# EMMC_with_rk399.net
KiCad netlist of a schematic drawn in Altium Designer
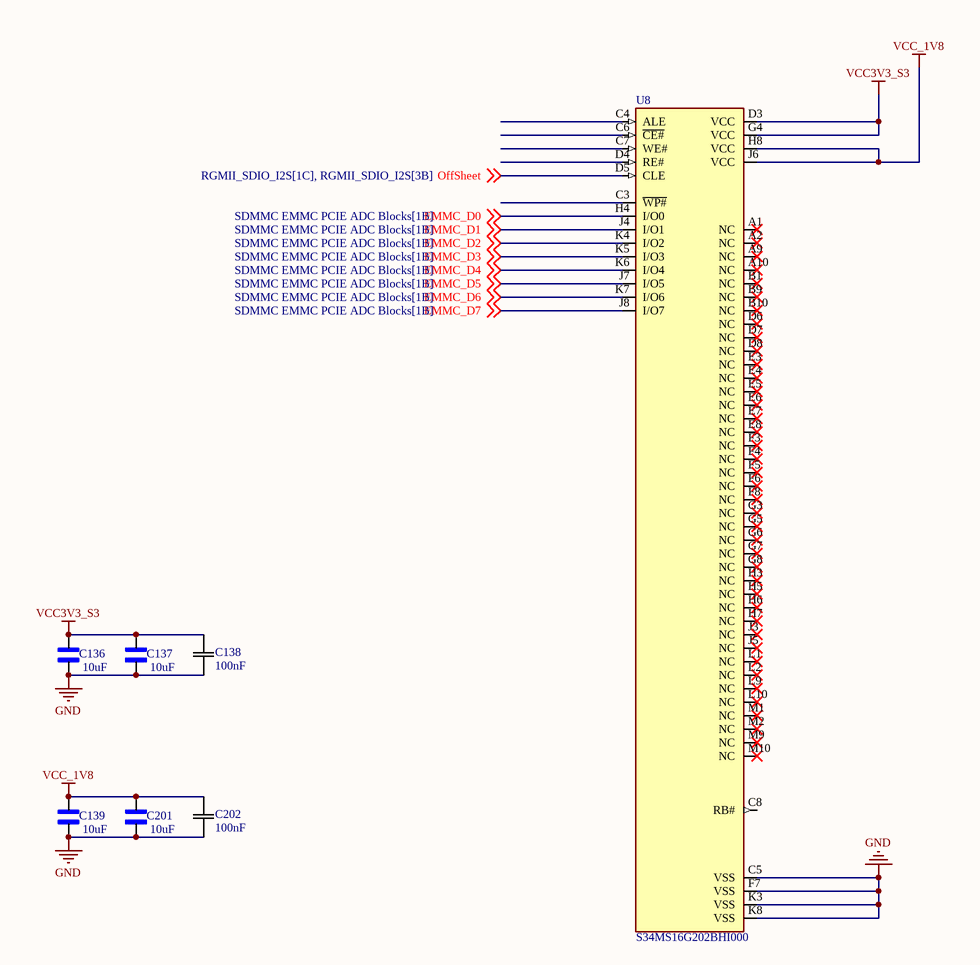
[diagram p0: EMMC with rk399.SchDoc]

(export (version "E")
  (design (tool "Eeschema 10.0.6"))
  (components
    (comp (ref "C136")
      (value "10uF")
      (footprint "CAPC1005X70N")
      (description "10 ÂµF Â±20% 6.3V Ceramic Capacitor X5R 0402 (1005 Metric)")
      (fields (field (name "MF") "Samsung") (field (name "MP") "CL05A106MQ5NUNC"))
      (libsource (lib "CL05A106MQ5NUNC") (part "CL05A106MQ5NUNC"))
    )
    (comp (ref "C137")
      (value "10uF")
      (footprint "CAPC1005X70N")
      (description "10 ÂµF Â±20% 6.3V Ceramic Capacitor X5R 0402 (1005 Metric)")
      (fields (field (name "MF") "Samsung") (field (name "MP") "CL05A106MQ5NUNC"))
      (libsource (lib "CL05A106MQ5NUNC") (part "CL05A106MQ5NUNC"))
    )
    (comp (ref "C138")
      (value "100nF")
      (footprint "CAP_1005_TDK")
      (description "Description")
      (fields
        (field (name "MANUFACTURER_PART_NUMBER") "C1005X7R1H104M050BB")
        (field (name "COPYRIGHT") "Copyright (C) 2025 Ultra Librarian. All rights reserved.")
      )
      (libsource (lib "C1005X7R1H104M050BB") (part "C1005X7R1H104M050BB"))
    )
    (comp (ref "C139")
      (value "10uF")
      (footprint "CAPC1005X70N")
      (description "10 ÂµF Â±20% 6.3V Ceramic Capacitor X5R 0402 (1005 Metric)")
      (fields (field (name "MF") "Samsung") (field (name "MP") "CL05A106MQ5NUNC"))
      (libsource (lib "CL05A106MQ5NUNC") (part "CL05A106MQ5NUNC"))
    )
    (comp (ref "C201")
      (value "10uF")
      (footprint "CAPC1005X70N")
      (description "10 ÂµF Â±20% 6.3V Ceramic Capacitor X5R 0402 (1005 Metric)")
      (fields (field (name "MF") "Samsung") (field (name "MP") "CL05A106MQ5NUNC"))
      (libsource (lib "CL05A106MQ5NUNC") (part "CL05A106MQ5NUNC"))
    )
    (comp (ref "C202")
      (value "100nF")
      (footprint "CAP_1005_TDK")
      (description "Description")
      (fields
        (field (name "MANUFACTURER_PART_NUMBER") "C1005X7R1H104M050BB")
        (field (name "COPYRIGHT") "Copyright (C) 2025 Ultra Librarian. All rights reserved.")
      )
      (libsource (lib "C1005X7R1H104M050BB") (part "C1005X7R1H104M050BB"))
    )
    (comp (ref "U8")
      (value "S34MS16G202BHI000")
      (footprint "BGA63C80P12X10_1100X900X120")
      (description "FLASH - NAND Memory IC 16Gb (4G x 4) Parallel 45 ns 63-BGA (11x9)")
      (fields (field (name "MF") "Cypress Semiconductor"))
      (libsource (lib "S34MS16G202BHI000") (part "S34MS16G202BHI000"))
    )
  )
  (nets
    (net (code "1") (name "EMMC_D0") (class "Default")
      (node (ref "U8") (pin "H4") (pinfunction "I/O0_H4") (pintype "bidirectional"))
    )
    (net (code "2") (name "EMMC_D1") (class "Default")
      (node (ref "U8") (pin "J4") (pinfunction "I/O1_J4") (pintype "bidirectional"))
    )
    (net (code "3") (name "EMMC_D2") (class "Default")
      (node (ref "U8") (pin "K4") (pinfunction "I/O2_K4") (pintype "bidirectional"))
    )
    (net (code "4") (name "EMMC_D3") (class "Default")
      (node (ref "U8") (pin "K5") (pinfunction "I/O3_K5") (pintype "bidirectional"))
    )
    (net (code "5") (name "EMMC_D4") (class "Default")
      (node (ref "U8") (pin "K6") (pinfunction "I/O4_K6") (pintype "bidirectional"))
    )
    (net (code "6") (name "EMMC_D5") (class "Default")
      (node (ref "U8") (pin "J7") (pinfunction "I/O5_J7") (pintype "bidirectional"))
    )
    (net (code "7") (name "EMMC_D6") (class "Default")
      (node (ref "U8") (pin "K7") (pinfunction "I/O6_K7") (pintype "bidirectional"))
    )
    (net (code "8") (name "EMMC_D7") (class "Default")
      (node (ref "U8") (pin "J8") (pinfunction "I/O7_J8") (pintype "bidirectional"))
    )
    (net (code "9") (name "GND") (class "Default")
      (node (ref "C136") (pin "1") (pinfunction "1_1") (pintype "passive"))
      (node (ref "C137") (pin "1") (pinfunction "1_1") (pintype "passive"))
      (node (ref "C138") (pin "2") (pinfunction "2_2") (pintype "passive"))
      (node (ref "C139") (pin "1") (pinfunction "1_1") (pintype "passive"))
      (node (ref "C201") (pin "1") (pinfunction "1_1") (pintype "passive"))
      (node (ref "C202") (pin "2") (pinfunction "2_2") (pintype "passive"))
      (node (ref "U8") (pin "C5") (pinfunction "VSS_C5") (pintype "power_in"))
      (node (ref "U8") (pin "F7") (pinfunction "VSS_F7") (pintype "power_in"))
      (node (ref "U8") (pin "K3") (pinfunction "VSS_K3") (pintype "power_in"))
      (node (ref "U8") (pin "K8") (pinfunction "VSS_K8") (pintype "power_in"))
    )
    (net (code "10") (name "OffSheet") (class "Default")
      (node (ref "U8") (pin "D5") (pinfunction "CLE_D5") (pintype "input"))
    )
    (net (code "11") (name "VCC3V3_S3") (class "Default")
      (node (ref "C136") (pin "2") (pinfunction "2_2") (pintype "passive"))
      (node (ref "C137") (pin "2") (pinfunction "2_2") (pintype "passive"))
      (node (ref "C138") (pin "1") (pinfunction "1_1") (pintype "passive"))
      (node (ref "U8") (pin "D3") (pinfunction "VCC_D3") (pintype "power_in"))
      (node (ref "U8") (pin "G4") (pinfunction "VCC_G4") (pintype "power_in"))
    )
    (net (code "12") (name "VCC_1V8") (class "Default")
      (node (ref "C139") (pin "2") (pinfunction "2_2") (pintype "passive"))
      (node (ref "C201") (pin "2") (pinfunction "2_2") (pintype "passive"))
      (node (ref "C202") (pin "1") (pinfunction "1_1") (pintype "passive"))
      (node (ref "U8") (pin "H8") (pinfunction "VCC_H8") (pintype "power_in"))
      (node (ref "U8") (pin "J6") (pinfunction "VCC_J6") (pintype "power_in"))
    )
    (net (code "13") (name "unconnected-(U8-ALE-PadC4)") (class "Default")
      (node (ref "U8") (pin "C4") (pinfunction "ALE_C4") (pintype "input"))
    )
    (net (code "14") (name "unconnected-(U8-NC-PadA1)") (class "Default")
      (node (ref "U8") (pin "A1") (pinfunction "NC_A1") (pintype "passive+no_connect"))
    )
    (net (code "15") (name "unconnected-(U8-NC-PadA2)") (class "Default")
      (node (ref "U8") (pin "A2") (pinfunction "NC_A2") (pintype "passive+no_connect"))
    )
    (net (code "16") (name "unconnected-(U8-NC-PadA9)") (class "Default")
      (node (ref "U8") (pin "A9") (pinfunction "NC_A9") (pintype "passive+no_connect"))
    )
    (net (code "17") (name "unconnected-(U8-NC-PadA10)") (class "Default")
      (node (ref "U8") (pin "A10") (pinfunction "NC_A10") (pintype "passive+no_connect"))
    )
    (net (code "18") (name "unconnected-(U8-NC-PadB1)") (class "Default")
      (node (ref "U8") (pin "B1") (pinfunction "NC_B1") (pintype "passive+no_connect"))
    )
    (net (code "19") (name "unconnected-(U8-NC-PadB9)") (class "Default")
      (node (ref "U8") (pin "B9") (pinfunction "NC_B9") (pintype "passive+no_connect"))
    )
    (net (code "20") (name "unconnected-(U8-NC-PadB10)") (class "Default")
      (node (ref "U8") (pin "B10") (pinfunction "NC_B10") (pintype "passive+no_connect"))
    )
    (net (code "21") (name "unconnected-(U8-NC-PadD6)") (class "Default")
      (node (ref "U8") (pin "D6") (pinfunction "NC_D6") (pintype "passive+no_connect"))
    )
    (net (code "22") (name "unconnected-(U8-NC-PadD7)") (class "Default")
      (node (ref "U8") (pin "D7") (pinfunction "NC_D7") (pintype "passive+no_connect"))
    )
    (net (code "23") (name "unconnected-(U8-NC-PadD8)") (class "Default")
      (node (ref "U8") (pin "D8") (pinfunction "NC_D8") (pintype "passive+no_connect"))
    )
    (net (code "24") (name "unconnected-(U8-NC-PadE3)") (class "Default")
      (node (ref "U8") (pin "E3") (pinfunction "NC_E3") (pintype "passive+no_connect"))
    )
    (net (code "25") (name "unconnected-(U8-NC-PadE4)") (class "Default")
      (node (ref "U8") (pin "E4") (pinfunction "NC_E4") (pintype "passive+no_connect"))
    )
    (net (code "26") (name "unconnected-(U8-NC-PadE5)") (class "Default")
      (node (ref "U8") (pin "E5") (pinfunction "NC_E5") (pintype "passive+no_connect"))
    )
    (net (code "27") (name "unconnected-(U8-NC-PadE6)") (class "Default")
      (node (ref "U8") (pin "E6") (pinfunction "NC_E6") (pintype "passive+no_connect"))
    )
    (net (code "28") (name "unconnected-(U8-NC-PadE7)") (class "Default")
      (node (ref "U8") (pin "E7") (pinfunction "NC_E7") (pintype "passive+no_connect"))
    )
    (net (code "29") (name "unconnected-(U8-NC-PadE8)") (class "Default")
      (node (ref "U8") (pin "E8") (pinfunction "NC_E8") (pintype "passive+no_connect"))
    )
    (net (code "30") (name "unconnected-(U8-NC-PadF3)") (class "Default")
      (node (ref "U8") (pin "F3") (pinfunction "NC_F3") (pintype "passive+no_connect"))
    )
    (net (code "31") (name "unconnected-(U8-NC-PadF4)") (class "Default")
      (node (ref "U8") (pin "F4") (pinfunction "NC_F4") (pintype "passive+no_connect"))
    )
    (net (code "32") (name "unconnected-(U8-NC-PadF5)") (class "Default")
      (node (ref "U8") (pin "F5") (pinfunction "NC_F5") (pintype "passive+no_connect"))
    )
    (net (code "33") (name "unconnected-(U8-NC-PadF6)") (class "Default")
      (node (ref "U8") (pin "F6") (pinfunction "NC_F6") (pintype "passive+no_connect"))
    )
    (net (code "34") (name "unconnected-(U8-NC-PadF8)") (class "Default")
      (node (ref "U8") (pin "F8") (pinfunction "NC_F8") (pintype "passive+no_connect"))
    )
    (net (code "35") (name "unconnected-(U8-NC-PadG3)") (class "Default")
      (node (ref "U8") (pin "G3") (pinfunction "NC_G3") (pintype "passive+no_connect"))
    )
    (net (code "36") (name "unconnected-(U8-NC-PadG5)") (class "Default")
      (node (ref "U8") (pin "G5") (pinfunction "NC_G5") (pintype "passive+no_connect"))
    )
    (net (code "37") (name "unconnected-(U8-NC-PadG6)") (class "Default")
      (node (ref "U8") (pin "G6") (pinfunction "NC_G6") (pintype "passive+no_connect"))
    )
    (net (code "38") (name "unconnected-(U8-NC-PadG7)") (class "Default")
      (node (ref "U8") (pin "G7") (pinfunction "NC_G7") (pintype "passive+no_connect"))
    )
    (net (code "39") (name "unconnected-(U8-NC-PadG8)") (class "Default")
      (node (ref "U8") (pin "G8") (pinfunction "NC_G8") (pintype "passive+no_connect"))
    )
    (net (code "40") (name "unconnected-(U8-NC-PadH3)") (class "Default")
      (node (ref "U8") (pin "H3") (pinfunction "NC_H3") (pintype "passive+no_connect"))
    )
    (net (code "41") (name "unconnected-(U8-NC-PadH5)") (class "Default")
      (node (ref "U8") (pin "H5") (pinfunction "NC_H5") (pintype "passive+no_connect"))
    )
    (net (code "42") (name "unconnected-(U8-NC-PadH6)") (class "Default")
      (node (ref "U8") (pin "H6") (pinfunction "NC_H6") (pintype "passive+no_connect"))
    )
    (net (code "43") (name "unconnected-(U8-NC-PadH7)") (class "Default")
      (node (ref "U8") (pin "H7") (pinfunction "NC_H7") (pintype "passive+no_connect"))
    )
    (net (code "44") (name "unconnected-(U8-NC-PadJ3)") (class "Default")
      (node (ref "U8") (pin "J3") (pinfunction "NC_J3") (pintype "passive+no_connect"))
    )
    (net (code "45") (name "unconnected-(U8-NC-PadJ5)") (class "Default")
      (node (ref "U8") (pin "J5") (pinfunction "NC_J5") (pintype "passive+no_connect"))
    )
    (net (code "46") (name "unconnected-(U8-NC-PadL1)") (class "Default")
      (node (ref "U8") (pin "L1") (pinfunction "NC_L1") (pintype "passive+no_connect"))
    )
    (net (code "47") (name "unconnected-(U8-NC-PadL2)") (class "Default")
      (node (ref "U8") (pin "L2") (pinfunction "NC_L2") (pintype "passive+no_connect"))
    )
    (net (code "48") (name "unconnected-(U8-NC-PadL9)") (class "Default")
      (node (ref "U8") (pin "L9") (pinfunction "NC_L9") (pintype "passive+no_connect"))
    )
    (net (code "49") (name "unconnected-(U8-NC-PadL10)") (class "Default")
      (node (ref "U8") (pin "L10") (pinfunction "NC_L10") (pintype "passive+no_connect"))
    )
    (net (code "50") (name "unconnected-(U8-NC-PadM1)") (class "Default")
      (node (ref "U8") (pin "M1") (pinfunction "NC_M1") (pintype "passive+no_connect"))
    )
    (net (code "51") (name "unconnected-(U8-NC-PadM2)") (class "Default")
      (node (ref "U8") (pin "M2") (pinfunction "NC_M2") (pintype "passive+no_connect"))
    )
    (net (code "52") (name "unconnected-(U8-NC-PadM9)") (class "Default")
      (node (ref "U8") (pin "M9") (pinfunction "NC_M9") (pintype "passive+no_connect"))
    )
    (net (code "53") (name "unconnected-(U8-NC-PadM10)") (class "Default")
      (node (ref "U8") (pin "M10") (pinfunction "NC_M10") (pintype "passive+no_connect"))
    )
    (net (code "54") (name "unconnected-(U8-RB#-PadC8)") (class "Default")
      (node (ref "U8") (pin "C8") (pinfunction "RB#_C8") (pintype "output"))
    )
    (net (code "55") (name "unconnected-(U8-RE#-PadD4)") (class "Default")
      (node (ref "U8") (pin "D4") (pinfunction "RE#_D4") (pintype "input"))
    )
    (net (code "56") (name "unconnected-(U8-WE#-PadC7)") (class "Default")
      (node (ref "U8") (pin "C7") (pinfunction "WE#_C7") (pintype "input"))
    )
    (net (code "57") (name "unconnected-(U8-~{CE#}-PadC6)") (class "Default")
      (node (ref "U8") (pin "C6") (pinfunction "~{CE#}_C6") (pintype "input"))
    )
    (net (code "58") (name "unconnected-(U8-~{WP#}-PadC3)") (class "Default")
      (node (ref "U8") (pin "C3") (pinfunction "~{WP#}_C3") (pintype "bidirectional"))
    )
  )
)
